# Ham-Dip-002.net
KiCad netlist of a schematic drawn in EAGLE
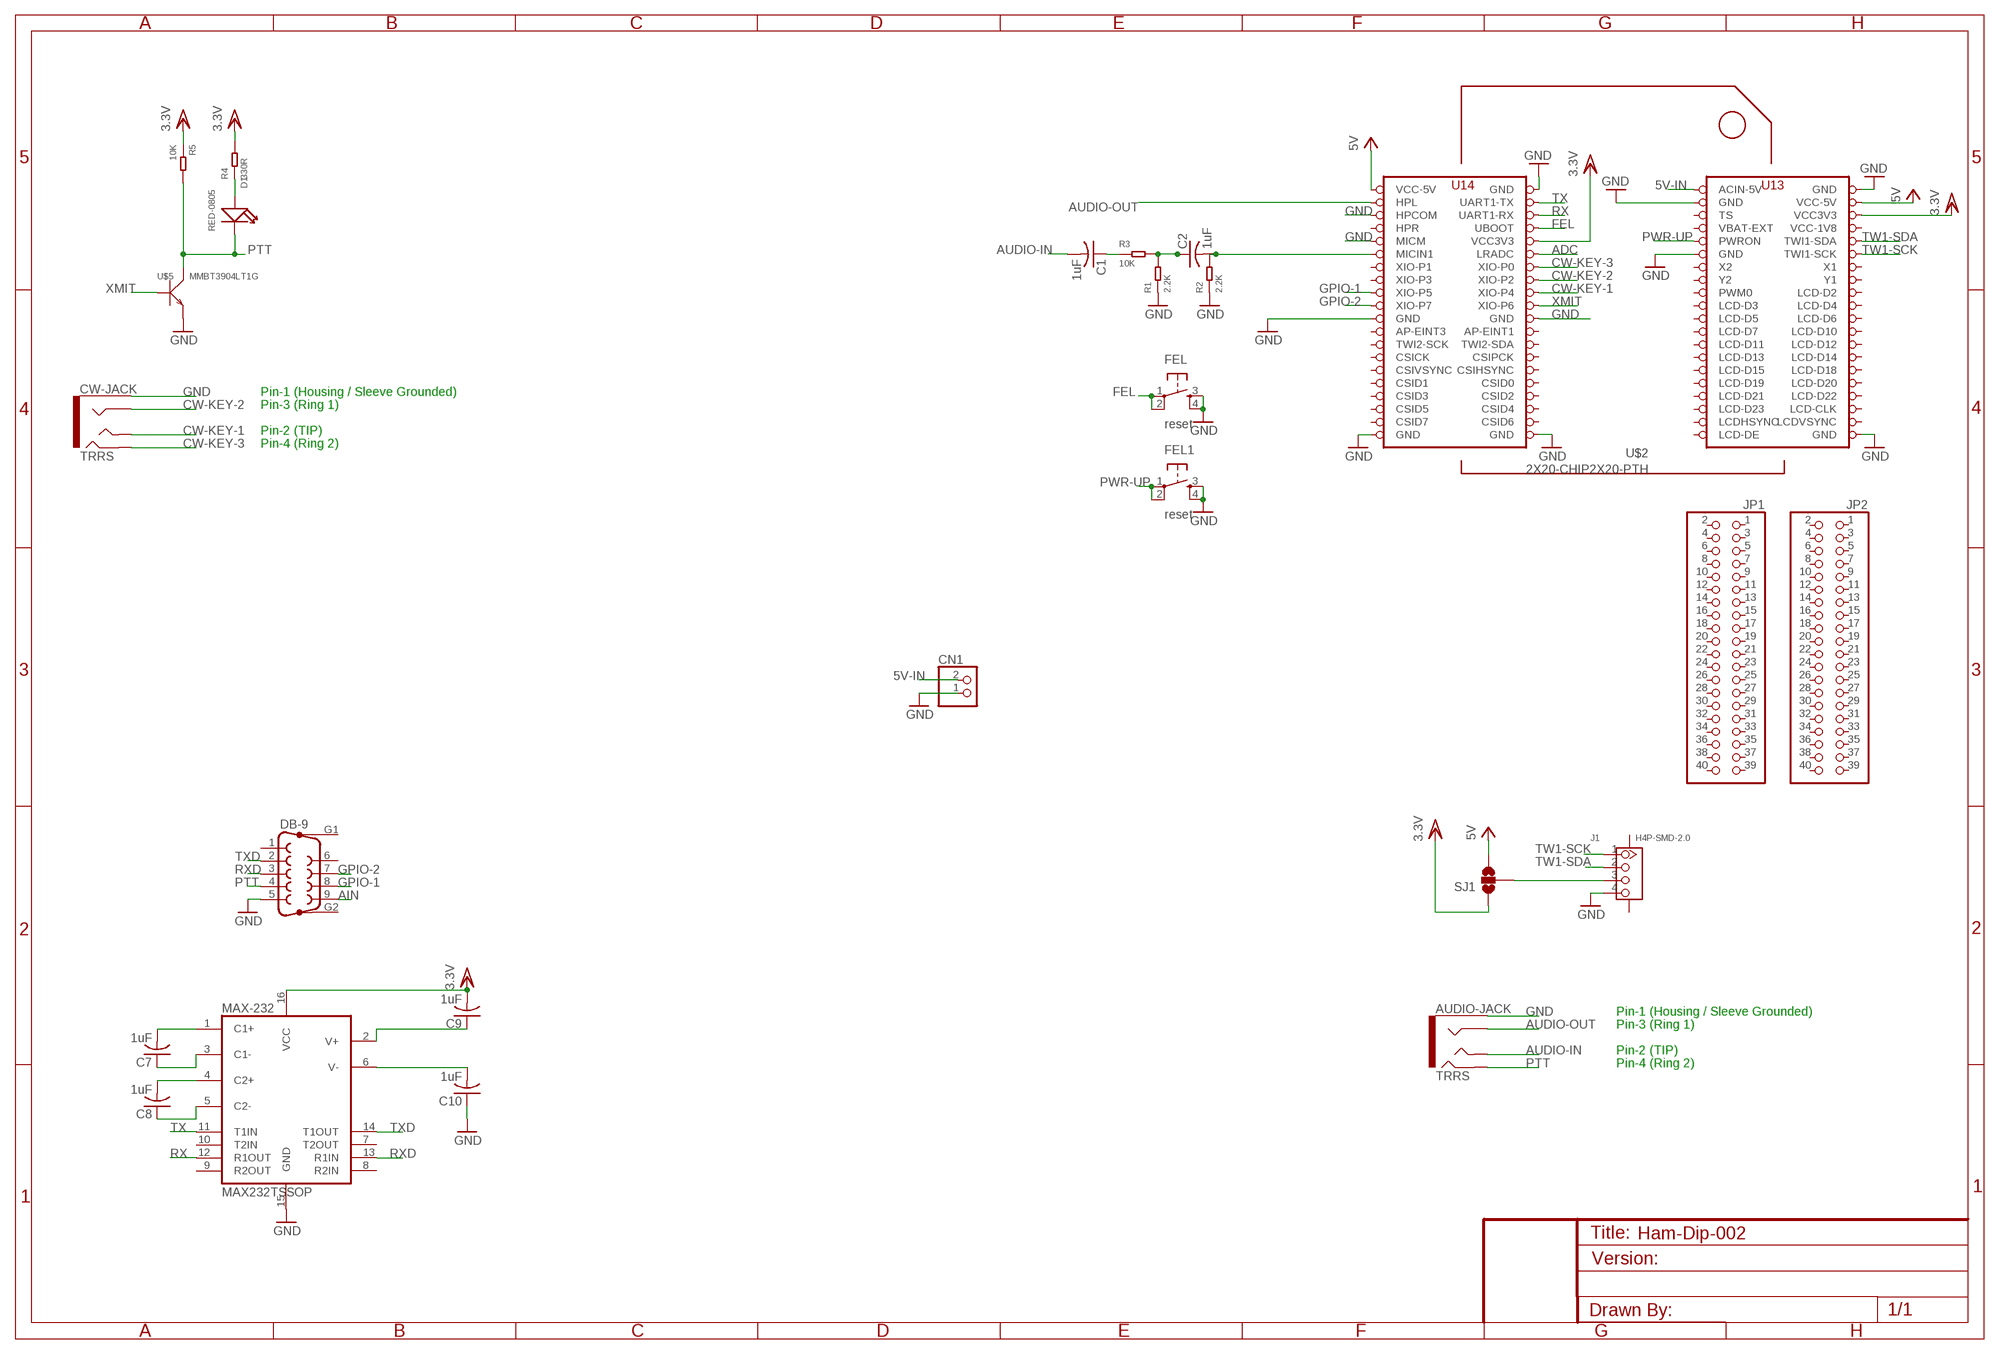
[diagram p0: schematic, sheet 1]

(export (version "E")
  (design (tool "Eeschema 10.0.6"))
  (components
    (comp (ref "AUDIO-JACK")
      (value "TRRS")
      (footprint "eagle-import:AUDIO-JACK-TRRS-SMD")
      (libsource (lib "eagle-import") (part "AUDIO-JACK3"))
    )
    (comp (ref "C1")
      (value "1uF")
      (footprint "eagle-import:C0805")
      (libsource (lib "eagle-import") (part "C-USC0805"))
    )
    (comp (ref "C2")
      (value "1uF")
      (footprint "eagle-import:C0805")
      (libsource (lib "eagle-import") (part "C-USC0805"))
    )
    (comp (ref "C7")
      (value "1uF")
      (footprint "eagle-import:C0805")
      (libsource (lib "eagle-import") (part "C-USC0805"))
    )
    (comp (ref "C8")
      (value "1uF")
      (footprint "eagle-import:C0805")
      (libsource (lib "eagle-import") (part "C-USC0805"))
    )
    (comp (ref "C9")
      (value "1uF")
      (footprint "eagle-import:C0805")
      (libsource (lib "eagle-import") (part "C-USC0805"))
    )
    (comp (ref "C10")
      (value "1uF")
      (footprint "eagle-import:C0805")
      (libsource (lib "eagle-import") (part "C-USC0805"))
    )
    (comp (ref "CN1")
      (value "JST_2PIN-SMT")
      (footprint "eagle-import:JST-PH-2-SMT")
      (libsource (lib "eagle-import") (part "JST_2PIN-SMT"))
    )
    (comp (ref "CW-JACK")
      (value "TRRS")
      (footprint "eagle-import:AUDIO-JACK-TRRS-SMD")
      (libsource (lib "eagle-import") (part "AUDIO-JACK3"))
    )
    (comp (ref "D1")
      (value "RED-0805")
      (footprint "eagle-import:LED-0805")
      (fields (field (name "MPN") "17-215SURC/S530-A2/TR8"))
      (libsource (lib "eagle-import") (part "SMD-LED-CLEAR-RED(0805)"))
    )
    (comp (ref "DB-9")
      (value "F09HP")
      (footprint "eagle-import:F09HP")
      (libsource (lib "eagle-import") (part "F09HP"))
    )
    (comp (ref "FEL")
      (value "reset")
      (footprint "eagle-import:TACTILE_SWITCH_SMD")
      (libsource (lib "eagle-import") (part "TAC_SWITCHSMD"))
    )
    (comp (ref "FEL1")
      (value "reset")
      (footprint "eagle-import:TACTILE_SWITCH_SMD")
      (libsource (lib "eagle-import") (part "TAC_SWITCHSMD"))
    )
    (comp (ref "J1")
      (value "H4P-SMD-2.0")
      (footprint "eagle-import:HW4-SMD-2.0")
      (libsource (lib "eagle-import") (part "GROVE-CONNECTOR-SMD(4+2P-2.0)"))
    )
    (comp (ref "JP1")
      (value "PINHD-2X20")
      (footprint "eagle-import:2X20")
      (libsource (lib "eagle-import") (part "PINHD-2X20"))
    )
    (comp (ref "JP2")
      (value "PINHD-2X20")
      (footprint "eagle-import:2X20")
      (libsource (lib "eagle-import") (part "PINHD-2X20"))
    )
    (comp (ref "MAX-232")
      (value "MAX232TSSOP")
      (footprint "eagle-import:TSSOP16")
      (libsource (lib "eagle-import") (part "MAX232TSSOP"))
    )
    (comp (ref "R1")
      (value "2.2K")
      (footprint "eagle-import:R0805")
      (fields (field (name "MPN") "RC0805JR-072K2L"))
      (libsource (lib "eagle-import") (part "SMD-RES-2.2K-5%-1/8W(0805)"))
    )
    (comp (ref "R2")
      (value "2.2K")
      (footprint "eagle-import:R0805")
      (fields (field (name "MPN") "RC0805JR-072K2L"))
      (libsource (lib "eagle-import") (part "SMD-RES-2.2K-5%-1/8W(0805)"))
    )
    (comp (ref "R3")
      (value "10K")
      (footprint "eagle-import:R0805")
      (fields (field (name "MPN") "RC0805FR-0710KL"))
      (libsource (lib "eagle-import") (part "SMD-RES-10K-1%-1/8W(0805)"))
    )
    (comp (ref "R4")
      (value "330R")
      (footprint "eagle-import:R0805")
      (fields (field (name "MPN") "RC0805JR-07220RL"))
      (libsource (lib "eagle-import") (part "SMD-RES-220R-5%-1/8W(0805)"))
    )
    (comp (ref "R5")
      (value "10K")
      (footprint "eagle-import:R0805")
      (fields (field (name "MPN") "RC0805FR-0710KL"))
      (libsource (lib "eagle-import") (part "SMD-RES-10K-1%-1/8W(0805)"))
    )
    (comp (ref "SJ1")
      (value "SMD_SJ_3WAY_OPENT")
      (footprint "eagle-import:SMD_SJ_3WAY_OPEN")
      (libsource (lib "eagle-import") (part "SMD_SJ_3WAY_OPENT"))
    )
    (comp (ref "U$2")
      (value "2X20-CHIP2X20-PTH")
      (footprint "eagle-import:2X20CHIP-TH")
      (fields (field (name "VENDOR_PART_NUMBER") "AWHW40-G-SMD-R (single)"))
      (libsource (lib "eagle-import") (part "2X20-CHIP2X20-PTH-CHIP_A"))
    )
    (comp (ref "U$5")
      (value "MMBT3904LT1G")
      (footprint "eagle-import:SOT-23")
      (libsource (lib "eagle-import") (part "SMD-TRANSISTORS-NPN-40V-200MA-MMBT3904LT1G(SOT-23)"))
    )
  )
  (nets
    (net (code "1") (name "/5V-IN") (class "Default")
      (node (ref "CN1") (pin "2") (pinfunction "1_2") (pintype "passive"))
      (node (ref "U$2") (pin "CHG-IN") (pinfunction "ACIN-5V_CHG-IN") (pintype "passive"))
    )
    (net (code "2") (name "/ADC") (class "Default")
      (node (ref "U$2") (pin "LRADC") (pinfunction "LRADC_LRADC") (pintype "passive"))
    )
    (net (code "3") (name "/AIN") (class "Default")
      (node (ref "DB-9") (pin "9") (pinfunction "9_9") (pintype "passive"))
    )
    (net (code "4") (name "/AUDIO-IN") (class "Default")
      (node (ref "AUDIO-JACK") (pin "TIP") (pinfunction "TIP_TIP") (pintype "bidirectional"))
      (node (ref "C1") (pin "2") (pinfunction "2_2") (pintype "passive"))
    )
    (net (code "5") (name "/AUDIO-OUT") (class "Default")
      (node (ref "AUDIO-JACK") (pin "RING1") (pinfunction "RING1_RING1") (pintype "bidirectional"))
      (node (ref "U$2") (pin "HPL") (pinfunction "HPL_HPL") (pintype "passive"))
    )
    (net (code "6") (name "/CW-KEY-1") (class "Default")
      (node (ref "CW-JACK") (pin "TIP") (pinfunction "TIP_TIP") (pintype "bidirectional"))
      (node (ref "U$2") (pin "XIO-P4") (pinfunction "XIO-P4_XIO-P4") (pintype "passive"))
    )
    (net (code "7") (name "/CW-KEY-2") (class "Default")
      (node (ref "CW-JACK") (pin "RING1") (pinfunction "RING1_RING1") (pintype "bidirectional"))
      (node (ref "U$2") (pin "XIO-P2") (pinfunction "XIO-P2_XIO-P2") (pintype "passive"))
    )
    (net (code "8") (name "/CW-KEY-3") (class "Default")
      (node (ref "CW-JACK") (pin "RING2") (pinfunction "RING2_RING2") (pintype "bidirectional"))
      (node (ref "U$2") (pin "XIO-P0") (pinfunction "XIO-P0_XIO-P0") (pintype "passive"))
    )
    (net (code "9") (name "/FEL") (class "Default")
      (node (ref "FEL") (pin "1") (pinfunction "1_1") (pintype "passive"))
      (node (ref "FEL") (pin "2") (pinfunction "2_2") (pintype "passive"))
      (node (ref "U$2") (pin "FEL") (pinfunction "UBOOT_FEL") (pintype "passive"))
    )
    (net (code "10") (name "/GPIO-1") (class "Default")
      (node (ref "DB-9") (pin "8") (pinfunction "8_8") (pintype "passive"))
      (node (ref "U$2") (pin "XIO-P5") (pinfunction "XIO-P5_XIO-P5") (pintype "passive"))
    )
    (net (code "11") (name "/GPIO-2") (class "Default")
      (node (ref "DB-9") (pin "7") (pinfunction "7_7") (pintype "passive"))
      (node (ref "U$2") (pin "XIO-P7") (pinfunction "XIO-P7_XIO-P7") (pintype "passive"))
    )
    (net (code "12") (name "/PTT") (class "Default")
      (node (ref "AUDIO-JACK") (pin "RING2") (pinfunction "RING2_RING2") (pintype "bidirectional"))
      (node (ref "D1") (pin "-") (pinfunction "-_-") (pintype "passive"))
      (node (ref "DB-9") (pin "4") (pinfunction "4_4") (pintype "passive"))
      (node (ref "R5") (pin "2") (pinfunction "2_2") (pintype "passive"))
      (node (ref "U$5") (pin "3") (pinfunction "C_3") (pintype "passive"))
    )
    (net (code "13") (name "/PWR-UP") (class "Default")
      (node (ref "FEL1") (pin "1") (pinfunction "1_1") (pintype "passive"))
      (node (ref "FEL1") (pin "2") (pinfunction "2_2") (pintype "passive"))
      (node (ref "U$2") (pin "PWRON") (pinfunction "PWRON_PWRON") (pintype "passive"))
    )
    (net (code "14") (name "/RX") (class "Default")
      (node (ref "MAX-232") (pin "12") (pinfunction "R1OUT_12") (pintype "output"))
      (node (ref "U$2") (pin "UART1-RX") (pinfunction "UART1-RX_UART1-RX") (pintype "passive"))
    )
    (net (code "15") (name "/RXD") (class "Default")
      (node (ref "DB-9") (pin "3") (pinfunction "3_3") (pintype "passive"))
      (node (ref "MAX-232") (pin "13") (pinfunction "R1IN_13") (pintype "input"))
    )
    (net (code "16") (name "/TW1-SCK") (class "Default")
      (node (ref "J1") (pin "1") (pinfunction "1_1") (pintype "bidirectional"))
      (node (ref "U$2") (pin "TWI1-SCK") (pinfunction "TWI1-SCK_TWI1-SCK") (pintype "passive"))
    )
    (net (code "17") (name "/TW1-SDA") (class "Default")
      (node (ref "J1") (pin "2") (pinfunction "2_2") (pintype "bidirectional"))
      (node (ref "U$2") (pin "TWI1-SDA") (pinfunction "TWI1-SDA_TWI1-SDA") (pintype "passive"))
    )
    (net (code "18") (name "/TX") (class "Default")
      (node (ref "MAX-232") (pin "11") (pinfunction "T1IN_11") (pintype "input"))
      (node (ref "U$2") (pin "UART1-TX") (pinfunction "UART1-TX_UART1-TX") (pintype "passive"))
    )
    (net (code "19") (name "/TXD") (class "Default")
      (node (ref "DB-9") (pin "2") (pinfunction "2_2") (pintype "passive"))
      (node (ref "MAX-232") (pin "14") (pinfunction "T1OUT_14") (pintype "output"))
    )
    (net (code "20") (name "/VCC-1V8") (class "Default")
      (node (ref "U$2") (pin "VCC1V8") (pinfunction "VCC-1V8_VCC1V8") (pintype "power_in"))
    )
    (net (code "21") (name "/XMIT") (class "Default")
      (node (ref "U$2") (pin "XIO-P6") (pinfunction "XIO-P6_XIO-P6") (pintype "passive"))
      (node (ref "U$5") (pin "1") (pinfunction "B_1") (pintype "passive"))
    )
    (net (code "22") (name "3.3V") (class "Default")
      (node (ref "C9") (pin "2") (pinfunction "2_2") (pintype "passive"))
      (node (ref "MAX-232") (pin "16") (pinfunction "VCC_16") (pintype "bidirectional"))
      (node (ref "R4") (pin "2") (pinfunction "2_2") (pintype "passive"))
      (node (ref "R5") (pin "1") (pinfunction "1_1") (pintype "passive"))
      (node (ref "SJ1") (pin "1") (pinfunction "1_1") (pintype "passive"))
      (node (ref "U$2") (pin "VCC3V3") (pinfunction "VCC3V3_VCC3V3") (pintype "power_in"))
      (node (ref "U$2") (pin "VCC3V3@1") (pinfunction "VCC3V3_VCC3V3@1") (pintype "power_in"))
    )
    (net (code "23") (name "5V") (class "Default")
      (node (ref "SJ1") (pin "3") (pinfunction "3_3") (pintype "passive"))
      (node (ref "U$2") (pin "VCC5V@0") (pinfunction "VCC-5V_VCC5V@0") (pintype "power_in"))
      (node (ref "U$2") (pin "VCC5V@1") (pinfunction "VCC-5V_VCC5V@1") (pintype "power_in"))
    )
    (net (code "24") (name "GND") (class "Default")
      (node (ref "AUDIO-JACK") (pin "EARTH") (pinfunction "EARTH_EARTH") (pintype "bidirectional"))
      (node (ref "C10") (pin "1") (pinfunction "1_1") (pintype "passive"))
      (node (ref "CN1") (pin "1") (pinfunction "2_1") (pintype "passive"))
      (node (ref "CW-JACK") (pin "EARTH") (pinfunction "EARTH_EARTH") (pintype "bidirectional"))
      (node (ref "DB-9") (pin "5") (pinfunction "5_5") (pintype "passive"))
      (node (ref "FEL") (pin "3") (pinfunction "3_3") (pintype "passive"))
      (node (ref "FEL") (pin "4") (pinfunction "4_4") (pintype "passive"))
      (node (ref "FEL1") (pin "3") (pinfunction "3_3") (pintype "passive"))
      (node (ref "FEL1") (pin "4") (pinfunction "4_4") (pintype "passive"))
      (node (ref "J1") (pin "4") (pinfunction "4_4") (pintype "bidirectional"))
      (node (ref "MAX-232") (pin "15") (pinfunction "GND_15") (pintype "bidirectional"))
      (node (ref "R1") (pin "1") (pinfunction "1_1") (pintype "passive"))
      (node (ref "R2") (pin "1") (pinfunction "1_1") (pintype "passive"))
      (node (ref "U$2") (pin "GND@1") (pinfunction "GND_GND@1") (pintype "power_in"))
      (node (ref "U$2") (pin "GND@10") (pinfunction "GND_GND@10") (pintype "power_in"))
      (node (ref "U$2") (pin "GND@2") (pinfunction "GND_GND@2") (pintype "power_in"))
      (node (ref "U$2") (pin "GND@3") (pinfunction "GND_GND@3") (pintype "power_in"))
      (node (ref "U$2") (pin "GND@4") (pinfunction "GND_GND@4") (pintype "power_in"))
      (node (ref "U$2") (pin "GND@5") (pinfunction "GND_GND@5") (pintype "power_in"))
      (node (ref "U$2") (pin "GND@6") (pinfunction "GND_GND@6") (pintype "power_in"))
      (node (ref "U$2") (pin "GND@7") (pinfunction "GND_GND@7") (pintype "power_in"))
      (node (ref "U$2") (pin "GND@8") (pinfunction "GND_GND@8") (pintype "power_in"))
      (node (ref "U$2") (pin "HPCOM") (pinfunction "HPCOM_HPCOM") (pintype "passive"))
      (node (ref "U$2") (pin "MICM") (pinfunction "MICM_MICM") (pintype "passive"))
      (node (ref "U$5") (pin "2") (pinfunction "E_2") (pintype "passive"))
    )
    (net (code "25") (name "Net-(C1-Pad1)") (class "Default")
      (node (ref "C1") (pin "1") (pinfunction "1_1") (pintype "passive"))
      (node (ref "R3") (pin "1") (pinfunction "1_1") (pintype "passive"))
    )
    (net (code "26") (name "Net-(C2-Pad1)") (class "Default")
      (node (ref "C2") (pin "1") (pinfunction "1_1") (pintype "passive"))
      (node (ref "R1") (pin "2") (pinfunction "2_2") (pintype "passive"))
      (node (ref "R3") (pin "2") (pinfunction "2_2") (pintype "passive"))
    )
    (net (code "27") (name "Net-(C2-Pad2)") (class "Default")
      (node (ref "C2") (pin "2") (pinfunction "2_2") (pintype "passive"))
      (node (ref "R2") (pin "2") (pinfunction "2_2") (pintype "passive"))
      (node (ref "U$2") (pin "MICIN1") (pinfunction "MICIN1_MICIN1") (pintype "passive"))
    )
    (net (code "28") (name "Net-(D1-Pad+)") (class "Default")
      (node (ref "D1") (pin "+") (pinfunction "+_+") (pintype "passive"))
      (node (ref "R4") (pin "1") (pinfunction "1_1") (pintype "passive"))
    )
    (net (code "29") (name "Net-(J1-Pad3)") (class "Default")
      (node (ref "J1") (pin "3") (pinfunction "3_3") (pintype "bidirectional"))
      (node (ref "SJ1") (pin "2") (pinfunction "2_2") (pintype "passive"))
    )
    (net (code "30") (name "Net-(MAX-232-C1+)") (class "Default")
      (node (ref "C7") (pin "2") (pinfunction "2_2") (pintype "passive"))
      (node (ref "MAX-232") (pin "1") (pinfunction "C1+_1") (pintype "bidirectional"))
    )
    (net (code "31") (name "Net-(MAX-232-C1-)") (class "Default")
      (node (ref "C7") (pin "1") (pinfunction "1_1") (pintype "passive"))
      (node (ref "MAX-232") (pin "3") (pinfunction "C1-_3") (pintype "bidirectional"))
    )
    (net (code "32") (name "Net-(MAX-232-C2+)") (class "Default")
      (node (ref "C8") (pin "2") (pinfunction "2_2") (pintype "passive"))
      (node (ref "MAX-232") (pin "4") (pinfunction "C2+_4") (pintype "bidirectional"))
    )
    (net (code "33") (name "Net-(MAX-232-C2-)") (class "Default")
      (node (ref "C8") (pin "1") (pinfunction "1_1") (pintype "passive"))
      (node (ref "MAX-232") (pin "5") (pinfunction "C2-_5") (pintype "bidirectional"))
    )
    (net (code "34") (name "Net-(MAX-232-V+)") (class "Default")
      (node (ref "C9") (pin "1") (pinfunction "1_1") (pintype "passive"))
      (node (ref "MAX-232") (pin "2") (pinfunction "V+_2") (pintype "bidirectional"))
    )
    (net (code "35") (name "Net-(MAX-232-V-)") (class "Default")
      (node (ref "C10") (pin "2") (pinfunction "2_2") (pintype "passive"))
      (node (ref "MAX-232") (pin "6") (pinfunction "V-_6") (pintype "bidirectional"))
    )
    (net (code "36") (name "unconnected-(DB-9-Pad1)") (class "Default")
      (node (ref "DB-9") (pin "1") (pinfunction "1_1") (pintype "passive"))
    )
    (net (code "37") (name "unconnected-(DB-9-Pad6)") (class "Default")
      (node (ref "DB-9") (pin "6") (pinfunction "6_6") (pintype "passive"))
    )
    (net (code "38") (name "unconnected-(DB-9-PadG1)") (class "Default")
      (node (ref "DB-9") (pin "G1") (pinfunction "G1_G1") (pintype "passive"))
    )
    (net (code "39") (name "unconnected-(DB-9-PadG2)") (class "Default")
      (node (ref "DB-9") (pin "G2") (pinfunction "G2_G2") (pintype "passive"))
    )
    (net (code "40") (name "unconnected-(J1-PadSS1)") (class "Default")
      (node (ref "J1") (pin "SS1") (pinfunction "SS1_SS1") (pintype "bidirectional"))
    )
    (net (code "41") (name "unconnected-(J1-PadSS2)") (class "Default")
      (node (ref "J1") (pin "SS2") (pinfunction "SS2_SS2") (pintype "bidirectional"))
    )
    (net (code "42") (name "unconnected-(JP1-Pad1)") (class "Default")
      (node (ref "JP1") (pin "1") (pinfunction "1_1") (pintype "passive"))
    )
    (net (code "43") (name "unconnected-(JP1-Pad2)") (class "Default")
      (node (ref "JP1") (pin "2") (pinfunction "2_2") (pintype "passive"))
    )
    (net (code "44") (name "unconnected-(JP1-Pad3)") (class "Default")
      (node (ref "JP1") (pin "3") (pinfunction "3_3") (pintype "passive"))
    )
    (net (code "45") (name "unconnected-(JP1-Pad4)") (class "Default")
      (node (ref "JP1") (pin "4") (pinfunction "4_4") (pintype "passive"))
    )
    (net (code "46") (name "unconnected-(JP1-Pad5)") (class "Default")
      (node (ref "JP1") (pin "5") (pinfunction "5_5") (pintype "passive"))
    )
    (net (code "47") (name "unconnected-(JP1-Pad6)") (class "Default")
      (node (ref "JP1") (pin "6") (pinfunction "6_6") (pintype "passive"))
    )
    (net (code "48") (name "unconnected-(JP1-Pad7)") (class "Default")
      (node (ref "JP1") (pin "7") (pinfunction "7_7") (pintype "passive"))
    )
    (net (code "49") (name "unconnected-(JP1-Pad8)") (class "Default")
      (node (ref "JP1") (pin "8") (pinfunction "8_8") (pintype "passive"))
    )
    (net (code "50") (name "unconnected-(JP1-Pad9)") (class "Default")
      (node (ref "JP1") (pin "9") (pinfunction "9_9") (pintype "passive"))
    )
    (net (code "51") (name "unconnected-(JP1-Pad10)") (class "Default")
      (node (ref "JP1") (pin "10") (pinfunction "10_10") (pintype "passive"))
    )
    (net (code "52") (name "unconnected-(JP1-Pad11)") (class "Default")
      (node (ref "JP1") (pin "11") (pinfunction "11_11") (pintype "passive"))
    )
    (net (code "53") (name "unconnected-(JP1-Pad12)") (class "Default")
      (node (ref "JP1") (pin "12") (pinfunction "12_12") (pintype "passive"))
    )
    (net (code "54") (name "unconnected-(JP1-Pad13)") (class "Default")
      (node (ref "JP1") (pin "13") (pinfunction "13_13") (pintype "passive"))
    )
    (net (code "55") (name "unconnected-(JP1-Pad14)") (class "Default")
      (node (ref "JP1") (pin "14") (pinfunction "14_14") (pintype "passive"))
    )
    (net (code "56") (name "unconnected-(JP1-Pad15)") (class "Default")
      (node (ref "JP1") (pin "15") (pinfunction "15_15") (pintype "passive"))
    )
    (net (code "57") (name "unconnected-(JP1-Pad16)") (class "Default")
      (node (ref "JP1") (pin "16") (pinfunction "16_16") (pintype "passive"))
    )
    (net (code "58") (name "unconnected-(JP1-Pad17)") (class "Default")
      (node (ref "JP1") (pin "17") (pinfunction "17_17") (pintype "passive"))
    )
    (net (code "59") (name "unconnected-(JP1-Pad18)") (class "Default")
      (node (ref "JP1") (pin "18") (pinfunction "18_18") (pintype "passive"))
    )
    (net (code "60") (name "unconnected-(JP1-Pad19)") (class "Default")
      (node (ref "JP1") (pin "19") (pinfunction "19_19") (pintype "passive"))
    )
    (net (code "61") (name "unconnected-(JP1-Pad20)") (class "Default")
      (node (ref "JP1") (pin "20") (pinfunction "20_20") (pintype "passive"))
    )
    (net (code "62") (name "unconnected-(JP1-Pad21)") (class "Default")
      (node (ref "JP1") (pin "21") (pinfunction "21_21") (pintype "passive"))
    )
    (net (code "63") (name "unconnected-(JP1-Pad22)") (class "Default")
      (node (ref "JP1") (pin "22") (pinfunction "22_22") (pintype "passive"))
    )
    (net (code "64") (name "unconnected-(JP1-Pad23)") (class "Default")
      (node (ref "JP1") (pin "23") (pinfunction "23_23") (pintype "passive"))
    )
    (net (code "65") (name "unconnected-(JP1-Pad24)") (class "Default")
      (node (ref "JP1") (pin "24") (pinfunction "24_24") (pintype "passive"))
    )
    (net (code "66") (name "unconnected-(JP1-Pad25)") (class "Default")
      (node (ref "JP1") (pin "25") (pinfunction "25_25") (pintype "passive"))
    )
    (net (code "67") (name "unconnected-(JP1-Pad26)") (class "Default")
      (node (ref "JP1") (pin "26") (pinfunction "26_26") (pintype "passive"))
    )
    (net (code "68") (name "unconnected-(JP1-Pad27)") (class "Default")
      (node (ref "JP1") (pin "27") (pinfunction "27_27") (pintype "passive"))
    )
    (net (code "69") (name "unconnected-(JP1-Pad28)") (class "Default")
      (node (ref "JP1") (pin "28") (pinfunction "28_28") (pintype "passive"))
    )
    (net (code "70") (name "unconnected-(JP1-Pad29)") (class "Default")
      (node (ref "JP1") (pin "29") (pinfunction "29_29") (pintype "passive"))
    )
    (net (code "71") (name "unconnected-(JP1-Pad30)") (class "Default")
      (node (ref "JP1") (pin "30") (pinfunction "30_30") (pintype "passive"))
    )
    (net (code "72") (name "unconnected-(JP1-Pad31)") (class "Default")
      (node (ref "JP1") (pin "31") (pinfunction "31_31") (pintype "passive"))
    )
    (net (code "73") (name "unconnected-(JP1-Pad32)") (class "Default")
      (node (ref "JP1") (pin "32") (pinfunction "32_32") (pintype "passive"))
    )
    (net (code "74") (name "unconnected-(JP1-Pad33)") (class "Default")
      (node (ref "JP1") (pin "33") (pinfunction "33_33") (pintype "passive"))
    )
    (net (code "75") (name "unconnected-(JP1-Pad34)") (class "Default")
      (node (ref "JP1") (pin "34") (pinfunction "34_34") (pintype "passive"))
    )
    (net (code "76") (name "unconnected-(JP1-Pad35)") (class "Default")
      (node (ref "JP1") (pin "35") (pinfunction "35_35") (pintype "passive"))
    )
    (net (code "77") (name "unconnected-(JP1-Pad36)") (class "Default")
      (node (ref "JP1") (pin "36") (pinfunction "36_36") (pintype "passive"))
    )
    (net (code "78") (name "unconnected-(JP1-Pad37)") (class "Default")
      (node (ref "JP1") (pin "37") (pinfunction "37_37") (pintype "passive"))
    )
    (net (code "79") (name "unconnected-(JP1-Pad38)") (class "Default")
      (node (ref "JP1") (pin "38") (pinfunction "38_38") (pintype "passive"))
    )
    (net (code "80") (name "unconnected-(JP1-Pad39)") (class "Default")
      (node (ref "JP1") (pin "39") (pinfunction "39_39") (pintype "passive"))
    )
    (net (code "81") (name "unconnected-(JP1-Pad40)") (class "Default")
      (node (ref "JP1") (pin "40") (pinfunction "40_40") (pintype "passive"))
    )
    (net (code "82") (name "unconnected-(JP2-Pad1)") (class "Default")
      (node (ref "JP2") (pin "1") (pinfunction "1_1") (pintype "passive"))
    )
    (net (code "83") (name "unconnected-(JP2-Pad2)") (class "Default")
      (node (ref "JP2") (pin "2") (pinfunction "2_2") (pintype "passive"))
    )
    (net (code "84") (name "unconnected-(JP2-Pad3)") (class "Default")
      (node (ref "JP2") (pin "3") (pinfunction "3_3") (pintype "passive"))
    )
    (net (code "85") (name "unconnected-(JP2-Pad4)") (class "Default")
      (node (ref "JP2") (pin "4") (pinfunction "4_4") (pintype "passive"))
    )
    (net (code "86") (name "unconnected-(JP2-Pad5)") (class "Default")
      (node (ref "JP2") (pin "5") (pinfunction "5_5") (pintype "passive"))
    )
    (net (code "87") (name "unconnected-(JP2-Pad6)") (class "Default")
      (node (ref "JP2") (pin "6") (pinfunction "6_6") (pintype "passive"))
    )
    (net (code "88") (name "unconnected-(JP2-Pad7)") (class "Default")
      (node (ref "JP2") (pin "7") (pinfunction "7_7") (pintype "passive"))
    )
    (net (code "89") (name "unconnected-(JP2-Pad8)") (class "Default")
      (node (ref "JP2") (pin "8") (pinfunction "8_8") (pintype "passive"))
    )
    (net (code "90") (name "unconnected-(JP2-Pad9)") (class "Default")
      (node (ref "JP2") (pin "9") (pinfunction "9_9") (pintype "passive"))
    )
    (net (code "91") (name "unconnected-(JP2-Pad10)") (class "Default")
      (node (ref "JP2") (pin "10") (pinfunction "10_10") (pintype "passive"))
    )
    (net (code "92") (name "unconnected-(JP2-Pad11)") (class "Default")
      (node (ref "JP2") (pin "11") (pinfunction "11_11") (pintype "passive"))
    )
    (net (code "93") (name "unconnected-(JP2-Pad12)") (class "Default")
      (node (ref "JP2") (pin "12") (pinfunction "12_12") (pintype "passive"))
    )
    (net (code "94") (name "unconnected-(JP2-Pad13)") (class "Default")
      (node (ref "JP2") (pin "13") (pinfunction "13_13") (pintype "passive"))
    )
    (net (code "95") (name "unconnected-(JP2-Pad14)") (class "Default")
      (node (ref "JP2") (pin "14") (pinfunction "14_14") (pintype "passive"))
    )
    (net (code "96") (name "unconnected-(JP2-Pad15)") (class "Default")
      (node (ref "JP2") (pin "15") (pinfunction "15_15") (pintype "passive"))
    )
    (net (code "97") (name "unconnected-(JP2-Pad16)") (class "Default")
      (node (ref "JP2") (pin "16") (pinfunction "16_16") (pintype "passive"))
    )
    (net (code "98") (name "unconnected-(JP2-Pad17)") (class "Default")
      (node (ref "JP2") (pin "17") (pinfunction "17_17") (pintype "passive"))
    )
    (net (code "99") (name "unconnected-(JP2-Pad18)") (class "Default")
      (node (ref "JP2") (pin "18") (pinfunction "18_18") (pintype "passive"))
    )
    (net (code "100") (name "unconnected-(JP2-Pad19)") (class "Default")
      (node (ref "JP2") (pin "19") (pinfunction "19_19") (pintype "passive"))
    )
    (net (code "101") (name "unconnected-(JP2-Pad20)") (class "Default")
      (node (ref "JP2") (pin "20") (pinfunction "20_20") (pintype "passive"))
    )
    (net (code "102") (name "unconnected-(JP2-Pad21)") (class "Default")
      (node (ref "JP2") (pin "21") (pinfunction "21_21") (pintype "passive"))
    )
    (net (code "103") (name "unconnected-(JP2-Pad22)") (class "Default")
      (node (ref "JP2") (pin "22") (pinfunction "22_22") (pintype "passive"))
    )
    (net (code "104") (name "unconnected-(JP2-Pad23)") (class "Default")
      (node (ref "JP2") (pin "23") (pinfunction "23_23") (pintype "passive"))
    )
    (net (code "105") (name "unconnected-(JP2-Pad24)") (class "Default")
      (node (ref "JP2") (pin "24") (pinfunction "24_24") (pintype "passive"))
    )
    (net (code "106") (name "unconnected-(JP2-Pad25)") (class "Default")
      (node (ref "JP2") (pin "25") (pinfunction "25_25") (pintype "passive"))
    )
    (net (code "107") (name "unconnected-(JP2-Pad26)") (class "Default")
      (node (ref "JP2") (pin "26") (pinfunction "26_26") (pintype "passive"))
    )
    (net (code "108") (name "unconnected-(JP2-Pad27)") (class "Default")
      (node (ref "JP2") (pin "27") (pinfunction "27_27") (pintype "passive"))
    )
    (net (code "109") (name "unconnected-(JP2-Pad28)") (class "Default")
      (node (ref "JP2") (pin "28") (pinfunction "28_28") (pintype "passive"))
    )
    (net (code "110") (name "unconnected-(JP2-Pad29)") (class "Default")
      (node (ref "JP2") (pin "29") (pinfunction "29_29") (pintype "passive"))
    )
    (net (code "111") (name "unconnected-(JP2-Pad30)") (class "Default")
      (node (ref "JP2") (pin "30") (pinfunction "30_30") (pintype "passive"))
    )
    (net (code "112") (name "unconnected-(JP2-Pad31)") (class "Default")
      (node (ref "JP2") (pin "31") (pinfunction "31_31") (pintype "passive"))
    )
    (net (code "113") (name "unconnected-(JP2-Pad32)") (class "Default")
      (node (ref "JP2") (pin "32") (pinfunction "32_32") (pintype "passive"))
    )
    (net (code "114") (name "unconnected-(JP2-Pad33)") (class "Default")
      (node (ref "JP2") (pin "33") (pinfunction "33_33") (pintype "passive"))
    )
    (net (code "115") (name "unconnected-(JP2-Pad34)") (class "Default")
      (node (ref "JP2") (pin "34") (pinfunction "34_34") (pintype "passive"))
    )
    (net (code "116") (name "unconnected-(JP2-Pad35)") (class "Default")
      (node (ref "JP2") (pin "35") (pinfunction "35_35") (pintype "passive"))
    )
    (net (code "117") (name "unconnected-(JP2-Pad36)") (class "Default")
      (node (ref "JP2") (pin "36") (pinfunction "36_36") (pintype "passive"))
    )
    (net (code "118") (name "unconnected-(JP2-Pad37)") (class "Default")
      (node (ref "JP2") (pin "37") (pinfunction "37_37") (pintype "passive"))
    )
    (net (code "119") (name "unconnected-(JP2-Pad38)") (class "Default")
      (node (ref "JP2") (pin "38") (pinfunction "38_38") (pintype "passive"))
    )
    (net (code "120") (name "unconnected-(JP2-Pad39)") (class "Default")
      (node (ref "JP2") (pin "39") (pinfunction "39_39") (pintype "passive"))
    )
    (net (code "121") (name "unconnected-(JP2-Pad40)") (class "Default")
      (node (ref "JP2") (pin "40") (pinfunction "40_40") (pintype "passive"))
    )
    (net (code "122") (name "unconnected-(MAX-232-R2IN-Pad8)") (class "Default")
      (node (ref "MAX-232") (pin "8") (pinfunction "R2IN_8") (pintype "input"))
    )
    (net (code "123") (name "unconnected-(MAX-232-R2OUT-Pad9)") (class "Default")
      (node (ref "MAX-232") (pin "9") (pinfunction "R2OUT_9") (pintype "output"))
    )
    (net (code "124") (name "unconnected-(MAX-232-T2IN-Pad10)") (class "Default")
      (node (ref "MAX-232") (pin "10") (pinfunction "T2IN_10") (pintype "input"))
    )
    (net (code "125") (name "unconnected-(MAX-232-T2OUT-Pad7)") (class "Default")
      (node (ref "MAX-232") (pin "7") (pinfunction "T2OUT_7") (pintype "output"))
    )
    (net (code "126") (name "unconnected-(U$2-LCDHSYNC-PadLCD-HSYNC)") (class "Default")
      (node (ref "U$2") (pin "LCD-HSYNC") (pinfunction "LCDHSYNC_LCD-HSYNC") (pintype "passive"))
    )
    (net (code "127") (name "unconnected-(U$2-LCDVSYNC-PadLCD-VSYNC)") (class "Default")
      (node (ref "U$2") (pin "LCD-VSYNC") (pinfunction "LCDVSYNC_LCD-VSYNC") (pintype "passive"))
    )
    (net (code "128") (name "unconnected-(U$2-PadAP-EINT1)") (class "Default")
      (node (ref "U$2") (pin "AP-EINT1") (pinfunction "AP-EINT1_AP-EINT1") (pintype "passive"))
    )
    (net (code "129") (name "unconnected-(U$2-PadAP-EINT3)") (class "Default")
      (node (ref "U$2") (pin "AP-EINT3") (pinfunction "AP-EINT3_AP-EINT3") (pintype "passive"))
    )
    (net (code "130") (name "unconnected-(U$2-PadCSICK)") (class "Default")
      (node (ref "U$2") (pin "CSICK") (pinfunction "CSICK_CSICK") (pintype "passive"))
    )
    (net (code "131") (name "unconnected-(U$2-PadCSID0)") (class "Default")
      (node (ref "U$2") (pin "CSID0") (pinfunction "CSID0_CSID0") (pintype "passive"))
    )
    (net (code "132") (name "unconnected-(U$2-PadCSID1)") (class "Default")
      (node (ref "U$2") (pin "CSID1") (pinfunction "CSID1_CSID1") (pintype "passive"))
    )
    (net (code "133") (name "unconnected-(U$2-PadCSID2)") (class "Default")
      (node (ref "U$2") (pin "CSID2") (pinfunction "CSID2_CSID2") (pintype "passive"))
    )
    (net (code "134") (name "unconnected-(U$2-PadCSID3)") (class "Default")
      (node (ref "U$2") (pin "CSID3") (pinfunction "CSID3_CSID3") (pintype "passive"))
    )
    (net (code "135") (name "unconnected-(U$2-PadCSID4)") (class "Default")
      (node (ref "U$2") (pin "CSID4") (pinfunction "CSID4_CSID4") (pintype "passive"))
    )
    (net (code "136") (name "unconnected-(U$2-PadCSID5)") (class "Default")
      (node (ref "U$2") (pin "CSID5") (pinfunction "CSID5_CSID5") (pintype "passive"))
    )
    (net (code "137") (name "unconnected-(U$2-PadCSID6)") (class "Default")
      (node (ref "U$2") (pin "CSID6") (pinfunction "CSID6_CSID6") (pintype "passive"))
    )
    (net (code "138") (name "unconnected-(U$2-PadCSID7)") (class "Default")
      (node (ref "U$2") (pin "CSID7") (pinfunction "CSID7_CSID7") (pintype "passive"))
    )
    (net (code "139") (name "unconnected-(U$2-PadCSIHSYNC)") (class "Default")
      (node (ref "U$2") (pin "CSIHSYNC") (pinfunction "CSIHSYNC_CSIHSYNC") (pintype "passive"))
    )
    (net (code "140") (name "unconnected-(U$2-PadCSIPCK)") (class "Default")
      (node (ref "U$2") (pin "CSIPCK") (pinfunction "CSIPCK_CSIPCK") (pintype "passive"))
    )
    (net (code "141") (name "unconnected-(U$2-PadCSIVSYNC)") (class "Default")
      (node (ref "U$2") (pin "CSIVSYNC") (pinfunction "CSIVSYNC_CSIVSYNC") (pintype "passive"))
    )
    (net (code "142") (name "unconnected-(U$2-PadHPR)") (class "Default")
      (node (ref "U$2") (pin "HPR") (pinfunction "HPR_HPR") (pintype "passive"))
    )
    (net (code "143") (name "unconnected-(U$2-PadLCD-CLK)") (class "Default")
      (node (ref "U$2") (pin "LCD-CLK") (pinfunction "LCD-CLK_LCD-CLK") (pintype "passive"))
    )
    (net (code "144") (name "unconnected-(U$2-PadLCD-D2)") (class "Default")
      (node (ref "U$2") (pin "LCD-D2") (pinfunction "LCD-D2_LCD-D2") (pintype "passive"))
    )
    (net (code "145") (name "unconnected-(U$2-PadLCD-D3)") (class "Default")
      (node (ref "U$2") (pin "LCD-D3") (pinfunction "LCD-D3_LCD-D3") (pintype "passive"))
    )
    (net (code "146") (name "unconnected-(U$2-PadLCD-D4)") (class "Default")
      (node (ref "U$2") (pin "LCD-D4") (pinfunction "LCD-D4_LCD-D4") (pintype "passive"))
    )
    (net (code "147") (name "unconnected-(U$2-PadLCD-D5)") (class "Default")
      (node (ref "U$2") (pin "LCD-D5") (pinfunction "LCD-D5_LCD-D5") (pintype "passive"))
    )
    (net (code "148") (name "unconnected-(U$2-PadLCD-D6)") (class "Default")
      (node (ref "U$2") (pin "LCD-D6") (pinfunction "LCD-D6_LCD-D6") (pintype "passive"))
    )
    (net (code "149") (name "unconnected-(U$2-PadLCD-D7)") (class "Default")
      (node (ref "U$2") (pin "LCD-D7") (pinfunction "LCD-D7_LCD-D7") (pintype "passive"))
    )
    (net (code "150") (name "unconnected-(U$2-PadLCD-D10)") (class "Default")
      (node (ref "U$2") (pin "LCD-D10") (pinfunction "LCD-D10_LCD-D10") (pintype "passive"))
    )
    (net (code "151") (name "unconnected-(U$2-PadLCD-D11)") (class "Default")
      (node (ref "U$2") (pin "LCD-D11") (pinfunction "LCD-D11_LCD-D11") (pintype "passive"))
    )
    (net (code "152") (name "unconnected-(U$2-PadLCD-D12)") (class "Default")
      (node (ref "U$2") (pin "LCD-D12") (pinfunction "LCD-D12_LCD-D12") (pintype "passive"))
    )
    (net (code "153") (name "unconnected-(U$2-PadLCD-D13)") (class "Default")
      (node (ref "U$2") (pin "LCD-D13") (pinfunction "LCD-D13_LCD-D13") (pintype "passive"))
    )
    (net (code "154") (name "unconnected-(U$2-PadLCD-D14)") (class "Default")
      (node (ref "U$2") (pin "LCD-D14") (pinfunction "LCD-D14_LCD-D14") (pintype "passive"))
    )
    (net (code "155") (name "unconnected-(U$2-PadLCD-D15)") (class "Default")
      (node (ref "U$2") (pin "LCD-D15") (pinfunction "LCD-D15_LCD-D15") (pintype "passive"))
    )
    (net (code "156") (name "unconnected-(U$2-PadLCD-D18)") (class "Default")
      (node (ref "U$2") (pin "LCD-D18") (pinfunction "LCD-D18_LCD-D18") (pintype "passive"))
    )
    (net (code "157") (name "unconnected-(U$2-PadLCD-D19)") (class "Default")
      (node (ref "U$2") (pin "LCD-D19") (pinfunction "LCD-D19_LCD-D19") (pintype "passive"))
    )
    (net (code "158") (name "unconnected-(U$2-PadLCD-D20)") (class "Default")
      (node (ref "U$2") (pin "LCD-D20") (pinfunction "LCD-D20_LCD-D20") (pintype "passive"))
    )
    (net (code "159") (name "unconnected-(U$2-PadLCD-D21)") (class "Default")
      (node (ref "U$2") (pin "LCD-D21") (pinfunction "LCD-D21_LCD-D21") (pintype "passive"))
    )
    (net (code "160") (name "unconnected-(U$2-PadLCD-D22)") (class "Default")
      (node (ref "U$2") (pin "LCD-D22") (pinfunction "LCD-D22_LCD-D22") (pintype "passive"))
    )
    (net (code "161") (name "unconnected-(U$2-PadLCD-D23)") (class "Default")
      (node (ref "U$2") (pin "LCD-D23") (pinfunction "LCD-D23_LCD-D23") (pintype "passive"))
    )
    (net (code "162") (name "unconnected-(U$2-PadLCD-DE)") (class "Default")
      (node (ref "U$2") (pin "LCD-DE") (pinfunction "LCD-DE_LCD-DE") (pintype "passive"))
    )
    (net (code "163") (name "unconnected-(U$2-PadPWM0)") (class "Default")
      (node (ref "U$2") (pin "PWM0") (pinfunction "PWM0_PWM0") (pintype "passive"))
    )
    (net (code "164") (name "unconnected-(U$2-PadTS)") (class "Default")
      (node (ref "U$2") (pin "TS") (pinfunction "TS_TS") (pintype "passive"))
    )
    (net (code "165") (name "unconnected-(U$2-PadTWI2-SCK)") (class "Default")
      (node (ref "U$2") (pin "TWI2-SCK") (pinfunction "TWI2-SCK_TWI2-SCK") (pintype "passive"))
    )
    (net (code "166") (name "unconnected-(U$2-PadTWI2-SDA)") (class "Default")
      (node (ref "U$2") (pin "TWI2-SDA") (pinfunction "TWI2-SDA_TWI2-SDA") (pintype "passive"))
    )
    (net (code "167") (name "unconnected-(U$2-PadX1)") (class "Default")
      (node (ref "U$2") (pin "X1") (pinfunction "X1_X1") (pintype "passive"))
    )
    (net (code "168") (name "unconnected-(U$2-PadX2)") (class "Default")
      (node (ref "U$2") (pin "X2") (pinfunction "X2_X2") (pintype "passive"))
    )
    (net (code "169") (name "unconnected-(U$2-PadXIO-P1)") (class "Default")
      (node (ref "U$2") (pin "XIO-P1") (pinfunction "XIO-P1_XIO-P1") (pintype "passive"))
    )
    (net (code "170") (name "unconnected-(U$2-PadXIO-P3)") (class "Default")
      (node (ref "U$2") (pin "XIO-P3") (pinfunction "XIO-P3_XIO-P3") (pintype "passive"))
    )
    (net (code "171") (name "unconnected-(U$2-PadY1)") (class "Default")
      (node (ref "U$2") (pin "Y1") (pinfunction "Y1_Y1") (pintype "passive"))
    )
    (net (code "172") (name "unconnected-(U$2-PadY2)") (class "Default")
      (node (ref "U$2") (pin "Y2") (pinfunction "Y2_Y2") (pintype "passive"))
    )
    (net (code "173") (name "unconnected-(U$2-VBAT-EXT-PadBAT)") (class "Default")
      (node (ref "U$2") (pin "BAT") (pinfunction "VBAT-EXT_BAT") (pintype "passive"))
    )
  )
)
